# MagusConnectors.net
KiCad netlist of a schematic drawn in EAGLE
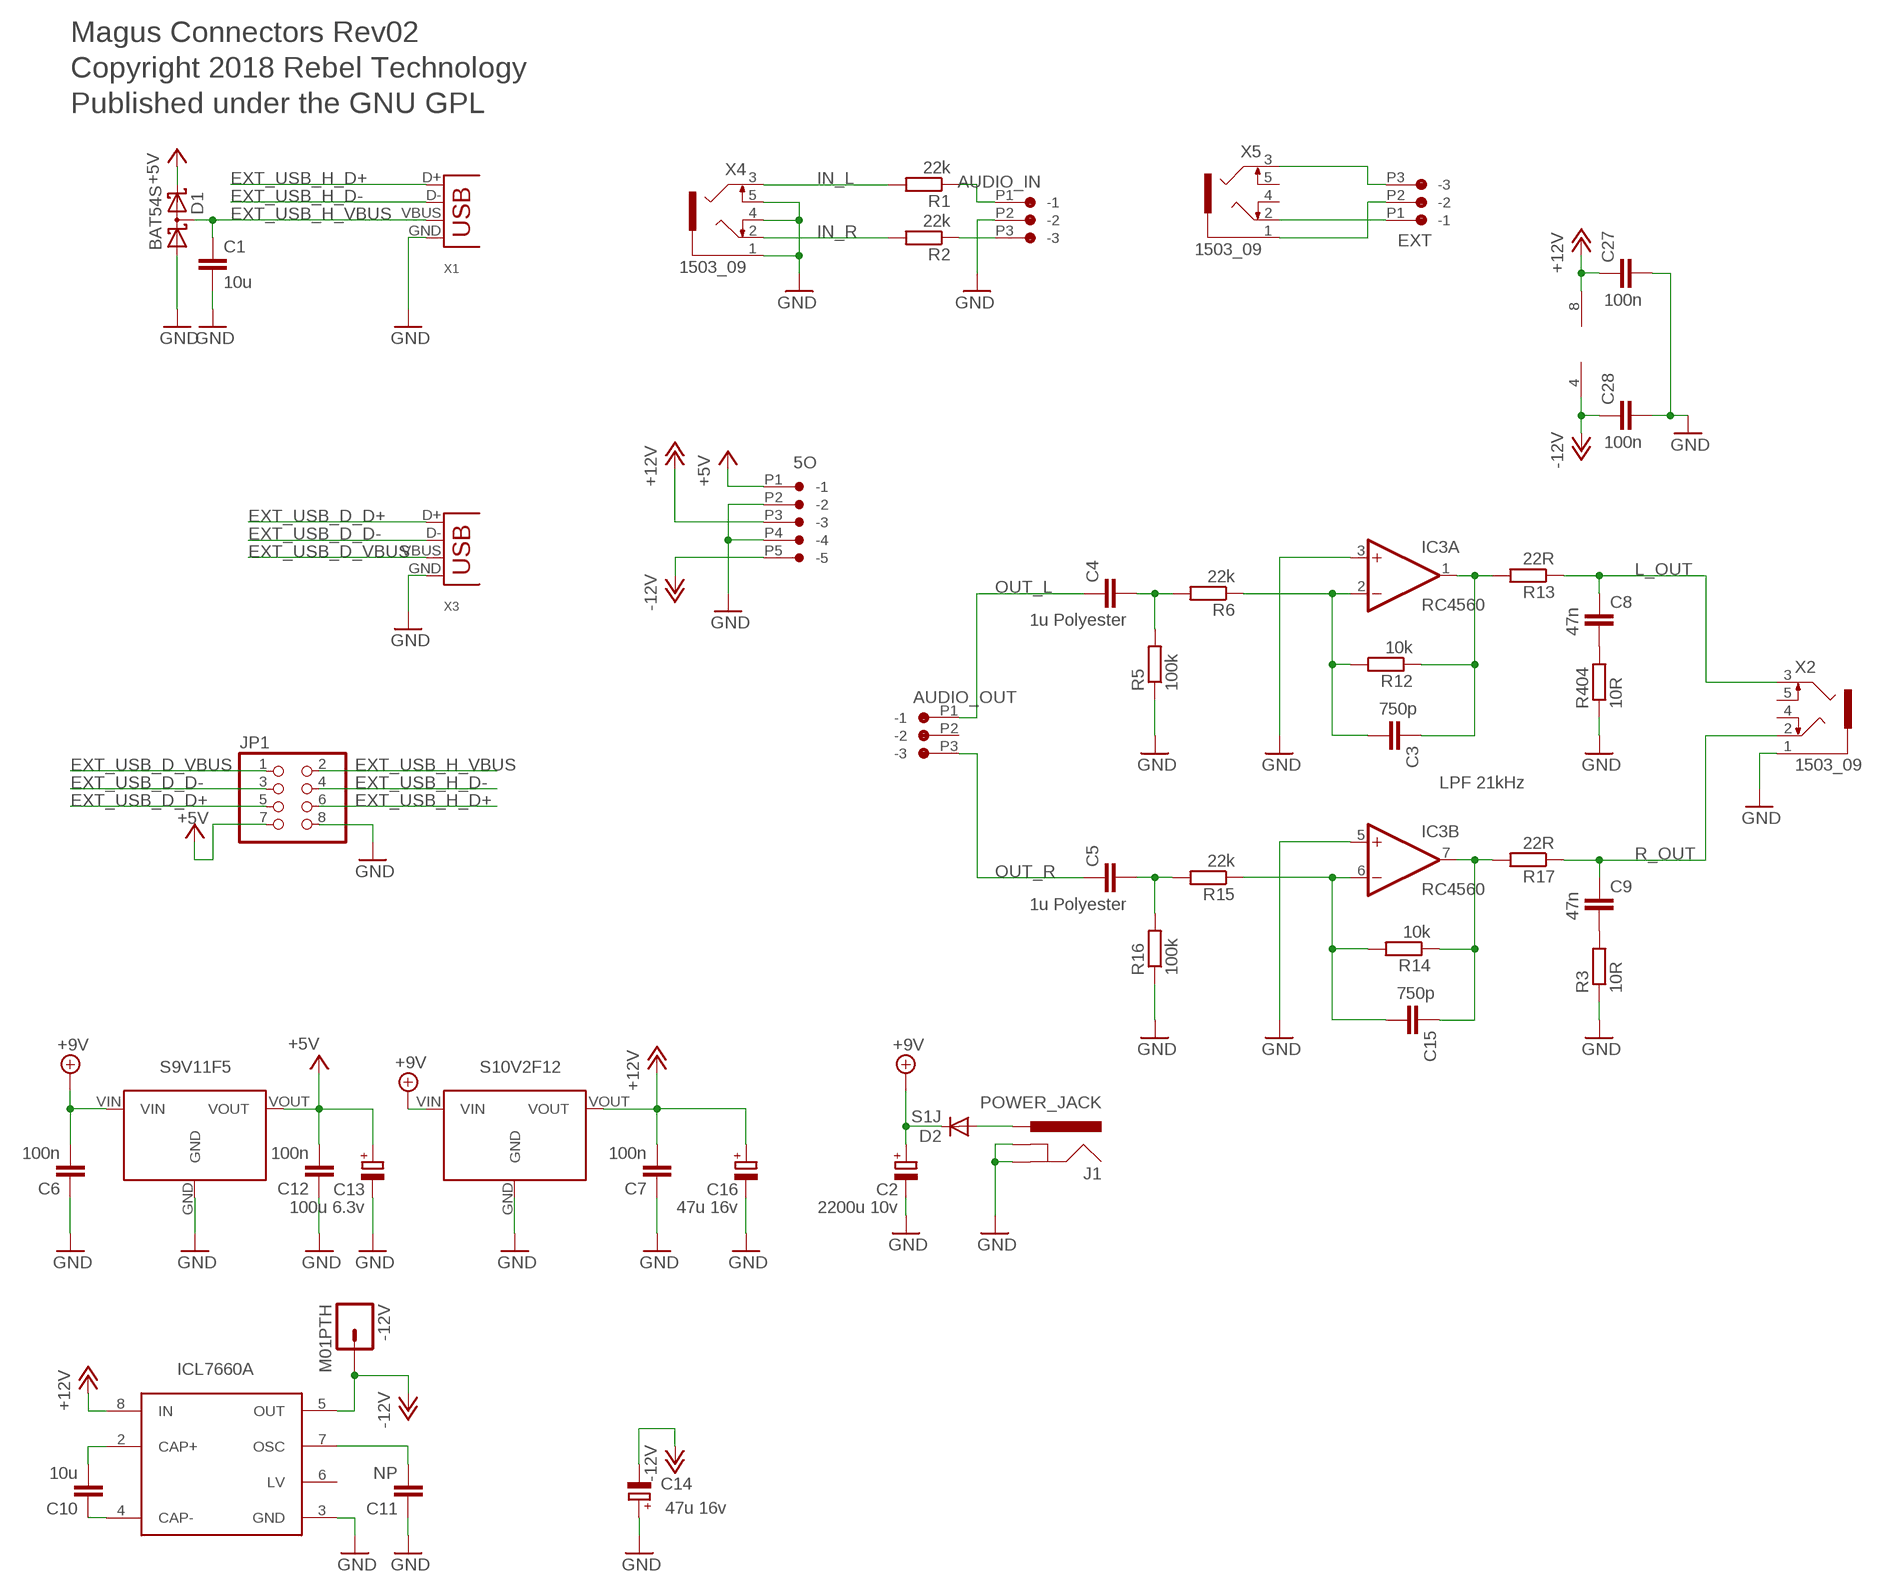
[diagram p0: schematic, sheet 1]

(export (version "E")
  (design (tool "Eeschema 10.0.6"))
  (components
    (comp (ref "-12V")
      (value "M01PTH")
      (footprint "eagle-import:1X01")
      (libsource (lib "eagle-import") (part "M01PTH"))
    )
    (comp (ref "5O")
      (value "CON-JST_PH_5W")
      (footprint "eagle-import:CON-JST_PH_5W")
      (libsource (lib "eagle-import") (part "CON-JST_PH_5W"))
    )
    (comp (ref "AUDIO_IN")
      (value "CON-JST_PH_3W")
      (footprint "eagle-import:CON-JST_PH_3W")
      (libsource (lib "eagle-import") (part "CON-JST_PH_3W"))
    )
    (comp (ref "AUDIO_OUT")
      (value "CON-JST_PH_3W")
      (footprint "eagle-import:CON-JST_PH_3W")
      (libsource (lib "eagle-import") (part "CON-JST_PH_3W"))
    )
    (comp (ref "C1")
      (value "10u")
      (footprint "eagle-import:C1206")
      (libsource (lib "eagle-import") (part "C-EUC1206"))
    )
    (comp (ref "C2")
      (value "2200u 10v")
      (footprint "eagle-import:PANASONIC_D")
      (libsource (lib "eagle-import") (part "CPOL-EUD"))
    )
    (comp (ref "C3")
      (value "750p")
      (footprint "eagle-import:C0603")
      (libsource (lib "eagle-import") (part "C-EUC0603"))
    )
    (comp (ref "C4")
      (value "1u Polyester")
      (footprint "eagle-import:C1210")
      (libsource (lib "eagle-import") (part "C-EUC1210"))
    )
    (comp (ref "C5")
      (value "1u Polyester")
      (footprint "eagle-import:C1210")
      (libsource (lib "eagle-import") (part "C-EUC1210"))
    )
    (comp (ref "C6")
      (value "100n")
      (footprint "eagle-import:C0603")
      (libsource (lib "eagle-import") (part "rcl_C-EUC0603"))
    )
    (comp (ref "C7")
      (value "100n")
      (footprint "eagle-import:C0603")
      (libsource (lib "eagle-import") (part "rcl_C-EUC0603"))
    )
    (comp (ref "C8")
      (value "47n")
      (footprint "eagle-import:C0603")
      (libsource (lib "eagle-import") (part "C-EUC0603"))
    )
    (comp (ref "C9")
      (value "47n")
      (footprint "eagle-import:C0603")
      (libsource (lib "eagle-import") (part "C-EUC0603"))
    )
    (comp (ref "C10")
      (value "10u")
      (footprint "eagle-import:C1206")
      (libsource (lib "eagle-import") (part "rcl_C-EUC1206"))
    )
    (comp (ref "C11")
      (value "NP")
      (footprint "eagle-import:C0603")
      (libsource (lib "eagle-import") (part "rcl_C-EUC0603"))
    )
    (comp (ref "C12")
      (value "100n")
      (footprint "eagle-import:C0603")
      (libsource (lib "eagle-import") (part "rcl_C-EUC0603"))
    )
    (comp (ref "C13")
      (value "100u 6.3v")
      (footprint "eagle-import:PANASONIC_B")
      (libsource (lib "eagle-import") (part "CPOL-EUB"))
    )
    (comp (ref "C14")
      (value "47u 16v")
      (footprint "eagle-import:PANASONIC_B")
      (libsource (lib "eagle-import") (part "CPOL-EUB"))
    )
    (comp (ref "C15")
      (value "750p")
      (footprint "eagle-import:C0603")
      (libsource (lib "eagle-import") (part "C-EUC0603"))
    )
    (comp (ref "C16")
      (value "47u 16v")
      (footprint "eagle-import:PANASONIC_B")
      (libsource (lib "eagle-import") (part "CPOL-EUB"))
    )
    (comp (ref "C27")
      (value "100n")
      (footprint "eagle-import:C0603")
      (libsource (lib "eagle-import") (part "C-EUC0603"))
    )
    (comp (ref "C28")
      (value "100n")
      (footprint "eagle-import:C0603")
      (libsource (lib "eagle-import") (part "C-EUC0603"))
    )
    (comp (ref "D1")
      (value "BAT54S")
      (footprint "eagle-import:SOT23")
      (libsource (lib "eagle-import") (part "BAT54S"))
    )
    (comp (ref "D2")
      (value "S1J")
      (footprint "eagle-import:SMA-DIODE")
      (libsource (lib "eagle-import") (part "DIODESMA"))
    )
    (comp (ref "EXT")
      (value "CON-JST_PH_3W")
      (footprint "eagle-import:CON-JST_PH_3W")
      (libsource (lib "eagle-import") (part "CON-JST_PH_3W"))
    )
    (comp (ref "IC3")
      (value "RC4560")
      (footprint "eagle-import:SO08")
      (libsource (lib "eagle-import") (part "NE5532D"))
    )
    (comp (ref "J1")
      (value "POWER_JACK")
      (footprint "eagle-import:DC_JACK_SLOT")
      (libsource (lib "eagle-import") (part "POWER_JACK"))
    )
    (comp (ref "JP1")
      (value "PINHD-2X4")
      (footprint "eagle-import:2X04")
      (libsource (lib "eagle-import") (part "PINHD-2X4"))
    )
    (comp (ref "R1")
      (value "22k")
      (footprint "eagle-import:R0603")
      (libsource (lib "eagle-import") (part "R-EU_R0603"))
    )
    (comp (ref "R2")
      (value "22k")
      (footprint "eagle-import:R0603")
      (libsource (lib "eagle-import") (part "R-EU_R0603"))
    )
    (comp (ref "R3")
      (value "10R")
      (footprint "eagle-import:R0603")
      (libsource (lib "eagle-import") (part "R-EU_R0603"))
    )
    (comp (ref "R5")
      (value "100k")
      (footprint "eagle-import:R0603")
      (libsource (lib "eagle-import") (part "R-EU_R0603"))
    )
    (comp (ref "R6")
      (value "22k")
      (footprint "eagle-import:R0603")
      (libsource (lib "eagle-import") (part "R-EU_R0603"))
    )
    (comp (ref "R12")
      (value "10k")
      (footprint "eagle-import:R0603")
      (libsource (lib "eagle-import") (part "R-EU_R0603"))
    )
    (comp (ref "R13")
      (value "22R")
      (footprint "eagle-import:R0603")
      (libsource (lib "eagle-import") (part "R-EU_R0603"))
    )
    (comp (ref "R14")
      (value "10k")
      (footprint "eagle-import:R0603")
      (libsource (lib "eagle-import") (part "R-EU_R0603"))
    )
    (comp (ref "R15")
      (value "22k")
      (footprint "eagle-import:R0603")
      (libsource (lib "eagle-import") (part "R-EU_R0603"))
    )
    (comp (ref "R16")
      (value "100k")
      (footprint "eagle-import:R0603")
      (libsource (lib "eagle-import") (part "R-EU_R0603"))
    )
    (comp (ref "R17")
      (value "22R")
      (footprint "eagle-import:R0603")
      (libsource (lib "eagle-import") (part "R-EU_R0603"))
    )
    (comp (ref "R404")
      (value "10R")
      (footprint "eagle-import:R0603")
      (libsource (lib "eagle-import") (part "R-EU_R0603"))
    )
    (comp (ref "U1")
      (value "S9V11F5")
      (footprint "eagle-import:REG_S9V11F5")
      (libsource (lib "eagle-import") (part "REG_S9V11F5"))
    )
    (comp (ref "U2")
      (value "S10V2F12")
      (footprint "eagle-import:REG_S9V11F5")
      (libsource (lib "eagle-import") (part "REG_S9V11F5"))
    )
    (comp (ref "U3")
      (value "ICL7660A")
      (footprint "eagle-import:SOIC8")
      (libsource (lib "eagle-import") (part "ICL7660"))
    )
    (comp (ref "X1")
      (value "USB-A-H")
      (footprint "eagle-import:USB-A-H")
      (libsource (lib "eagle-import") (part "USB-A-H"))
    )
    (comp (ref "X2")
      (value "1503_09")
      (footprint "eagle-import:1503_09")
      (libsource (lib "eagle-import") (part "1503_09"))
    )
    (comp (ref "X3")
      (value "USB-B-H")
      (footprint "eagle-import:USB-B-H")
      (libsource (lib "eagle-import") (part "USB-B-H"))
    )
    (comp (ref "X4")
      (value "1503_09")
      (footprint "eagle-import:1503_09")
      (libsource (lib "eagle-import") (part "1503_09"))
    )
    (comp (ref "X5")
      (value "1503_09")
      (footprint "eagle-import:1503_09")
      (libsource (lib "eagle-import") (part "1503_09"))
    )
  )
  (nets
    (net (code "1") (name "+5V") (class "Default")
      (node (ref "5O") (pin "P1") (pinfunction "-1_P1") (pintype "bidirectional"))
      (node (ref "C12") (pin "2") (pinfunction "2_2") (pintype "passive"))
      (node (ref "C13") (pin "+") (pinfunction "+_+") (pintype "passive"))
      (node (ref "D1") (pin "2") (pinfunction "C2_2") (pintype "passive"))
      (node (ref "JP1") (pin "7") (pinfunction "7_7") (pintype "passive"))
      (node (ref "U1") (pin "VOUT") (pinfunction "VOUT_VOUT") (pintype "output"))
    )
    (net (code "2") (name "+9V") (class "Default")
      (node (ref "C2") (pin "+") (pinfunction "+_+") (pintype "passive"))
      (node (ref "C6") (pin "2") (pinfunction "2_2") (pintype "passive"))
      (node (ref "D2") (pin "C") (pinfunction "C_C") (pintype "passive"))
      (node (ref "U1") (pin "VIN") (pinfunction "VIN_VIN") (pintype "input"))
      (node (ref "U2") (pin "VIN") (pinfunction "VIN_VIN") (pintype "input"))
    )
    (net (code "3") (name "+12V") (class "Default")
      (node (ref "5O") (pin "P3") (pinfunction "-3_P3") (pintype "bidirectional"))
      (node (ref "C16") (pin "+") (pinfunction "+_+") (pintype "passive"))
      (node (ref "C27") (pin "1") (pinfunction "1_1") (pintype "passive"))
      (node (ref "C7") (pin "2") (pinfunction "2_2") (pintype "passive"))
      (node (ref "IC3") (pin "8") (pinfunction "V+_8") (pintype "power_in"))
      (node (ref "U2") (pin "VOUT") (pinfunction "VOUT_VOUT") (pintype "output"))
      (node (ref "U3") (pin "8") (pinfunction "IN_8") (pintype "bidirectional"))
    )
    (net (code "4") (name "-12V") (class "Default")
      (node (ref "-12V") (pin "1") (pinfunction "1_1") (pintype "passive"))
      (node (ref "5O") (pin "P5") (pinfunction "-5_P5") (pintype "bidirectional"))
      (node (ref "C14") (pin "-") (pinfunction "-_-") (pintype "passive"))
      (node (ref "C28") (pin "1") (pinfunction "1_1") (pintype "passive"))
      (node (ref "IC3") (pin "4") (pinfunction "V-_4") (pintype "power_in"))
      (node (ref "U3") (pin "5") (pinfunction "OUT_5") (pintype "bidirectional"))
    )
    (net (code "5") (name "/EXT_USB_D_D+") (class "Default")
      (node (ref "JP1") (pin "5") (pinfunction "5_5") (pintype "passive"))
      (node (ref "X3") (pin "D+") (pinfunction "D+_D+") (pintype "bidirectional"))
    )
    (net (code "6") (name "/EXT_USB_D_D-") (class "Default")
      (node (ref "JP1") (pin "3") (pinfunction "3_3") (pintype "passive"))
      (node (ref "X3") (pin "D-") (pinfunction "D-_D-") (pintype "bidirectional"))
    )
    (net (code "7") (name "/EXT_USB_D_VBUS") (class "Default")
      (node (ref "JP1") (pin "1") (pinfunction "1_1") (pintype "passive"))
      (node (ref "X3") (pin "VBUS") (pinfunction "VBUS_VBUS") (pintype "bidirectional"))
    )
    (net (code "8") (name "/EXT_USB_H_D+") (class "Default")
      (node (ref "JP1") (pin "6") (pinfunction "6_6") (pintype "passive"))
      (node (ref "X1") (pin "D+") (pinfunction "D+_D+") (pintype "bidirectional"))
    )
    (net (code "9") (name "/EXT_USB_H_D-") (class "Default")
      (node (ref "JP1") (pin "4") (pinfunction "4_4") (pintype "passive"))
      (node (ref "X1") (pin "D-") (pinfunction "D-_D-") (pintype "bidirectional"))
    )
    (net (code "10") (name "/EXT_USB_H_VBUS") (class "Default")
      (node (ref "C1") (pin "1") (pinfunction "1_1") (pintype "passive"))
      (node (ref "D1") (pin "3") (pinfunction "C1A2_3") (pintype "passive"))
      (node (ref "JP1") (pin "2") (pinfunction "2_2") (pintype "passive"))
      (node (ref "X1") (pin "VBUS") (pinfunction "VBUS_VBUS") (pintype "bidirectional"))
    )
    (net (code "11") (name "/IN_L") (class "Default")
      (node (ref "R1") (pin "2") (pinfunction "2_2") (pintype "passive"))
      (node (ref "X4") (pin "3") (pinfunction "3_3") (pintype "passive"))
    )
    (net (code "12") (name "/IN_R") (class "Default")
      (node (ref "R2") (pin "2") (pinfunction "2_2") (pintype "passive"))
      (node (ref "X4") (pin "2") (pinfunction "2_2") (pintype "passive"))
    )
    (net (code "13") (name "/L_OUT") (class "Default")
      (node (ref "C8") (pin "1") (pinfunction "1_1") (pintype "passive"))
      (node (ref "R13") (pin "1") (pinfunction "1_1") (pintype "passive"))
      (node (ref "X2") (pin "3") (pinfunction "3_3") (pintype "passive"))
    )
    (net (code "14") (name "/OUT_L") (class "Default")
      (node (ref "AUDIO_OUT") (pin "P1") (pinfunction "-1_P1") (pintype "bidirectional"))
      (node (ref "C4") (pin "1") (pinfunction "1_1") (pintype "passive"))
    )
    (net (code "15") (name "/OUT_R") (class "Default")
      (node (ref "AUDIO_OUT") (pin "P3") (pinfunction "-3_P3") (pintype "bidirectional"))
      (node (ref "C5") (pin "1") (pinfunction "1_1") (pintype "passive"))
    )
    (net (code "16") (name "/R_OUT") (class "Default")
      (node (ref "C9") (pin "1") (pinfunction "1_1") (pintype "passive"))
      (node (ref "R17") (pin "1") (pinfunction "1_1") (pintype "passive"))
      (node (ref "X2") (pin "2") (pinfunction "2_2") (pintype "passive"))
    )
    (net (code "17") (name "GND") (class "Default")
      (node (ref "5O") (pin "P2") (pinfunction "-2_P2") (pintype "bidirectional"))
      (node (ref "5O") (pin "P4") (pinfunction "-4_P4") (pintype "bidirectional"))
      (node (ref "AUDIO_IN") (pin "P2") (pinfunction "-2_P2") (pintype "bidirectional"))
      (node (ref "C1") (pin "2") (pinfunction "2_2") (pintype "passive"))
      (node (ref "C11") (pin "1") (pinfunction "1_1") (pintype "passive"))
      (node (ref "C12") (pin "1") (pinfunction "1_1") (pintype "passive"))
      (node (ref "C13") (pin "-") (pinfunction "-_-") (pintype "passive"))
      (node (ref "C14") (pin "+") (pinfunction "+_+") (pintype "passive"))
      (node (ref "C16") (pin "-") (pinfunction "-_-") (pintype "passive"))
      (node (ref "C2") (pin "-") (pinfunction "-_-") (pintype "passive"))
      (node (ref "C27") (pin "2") (pinfunction "2_2") (pintype "passive"))
      (node (ref "C28") (pin "2") (pinfunction "2_2") (pintype "passive"))
      (node (ref "C6") (pin "1") (pinfunction "1_1") (pintype "passive"))
      (node (ref "C7") (pin "1") (pinfunction "1_1") (pintype "passive"))
      (node (ref "D1") (pin "1") (pinfunction "A1_1") (pintype "passive"))
      (node (ref "IC3") (pin "3") (pinfunction "+IN_3") (pintype "input"))
      (node (ref "IC3") (pin "5") (pinfunction "+IN_5") (pintype "input"))
      (node (ref "J1") (pin "GND") (pinfunction "GND_GND") (pintype "bidirectional"))
      (node (ref "J1") (pin "GNDBREAK") (pinfunction "GNDBREAK_GNDBREAK") (pintype "bidirectional"))
      (node (ref "JP1") (pin "8") (pinfunction "8_8") (pintype "passive"))
      (node (ref "R16") (pin "1") (pinfunction "1_1") (pintype "passive"))
      (node (ref "R3") (pin "1") (pinfunction "1_1") (pintype "passive"))
      (node (ref "R404") (pin "1") (pinfunction "1_1") (pintype "passive"))
      (node (ref "R5") (pin "1") (pinfunction "1_1") (pintype "passive"))
      (node (ref "U1") (pin "GND") (pinfunction "GND_GND") (pintype "power_in"))
      (node (ref "U2") (pin "GND") (pinfunction "GND_GND") (pintype "power_in"))
      (node (ref "U3") (pin "3") (pinfunction "GND_3") (pintype "bidirectional"))
      (node (ref "X1") (pin "GND") (pinfunction "GND_GND") (pintype "bidirectional"))
      (node (ref "X2") (pin "1") (pinfunction "1_1") (pintype "passive"))
      (node (ref "X3") (pin "GND") (pinfunction "GND_GND") (pintype "bidirectional"))
      (node (ref "X4") (pin "1") (pinfunction "1_1") (pintype "passive"))
      (node (ref "X4") (pin "4") (pinfunction "4_4") (pintype "passive"))
      (node (ref "X4") (pin "5") (pinfunction "5_5") (pintype "passive"))
    )
    (net (code "18") (name "Net-(AUDIO_IN--1)") (class "Default")
      (node (ref "AUDIO_IN") (pin "P1") (pinfunction "-1_P1") (pintype "bidirectional"))
      (node (ref "R1") (pin "1") (pinfunction "1_1") (pintype "passive"))
    )
    (net (code "19") (name "Net-(AUDIO_IN--3)") (class "Default")
      (node (ref "AUDIO_IN") (pin "P3") (pinfunction "-3_P3") (pintype "bidirectional"))
      (node (ref "R2") (pin "1") (pinfunction "1_1") (pintype "passive"))
    )
    (net (code "20") (name "Net-(C4-Pad2)") (class "Default")
      (node (ref "C4") (pin "2") (pinfunction "2_2") (pintype "passive"))
      (node (ref "R5") (pin "2") (pinfunction "2_2") (pintype "passive"))
      (node (ref "R6") (pin "2") (pinfunction "2_2") (pintype "passive"))
    )
    (net (code "21") (name "Net-(C5-Pad2)") (class "Default")
      (node (ref "C5") (pin "2") (pinfunction "2_2") (pintype "passive"))
      (node (ref "R15") (pin "2") (pinfunction "2_2") (pintype "passive"))
      (node (ref "R16") (pin "2") (pinfunction "2_2") (pintype "passive"))
    )
    (net (code "22") (name "Net-(C8-Pad2)") (class "Default")
      (node (ref "C8") (pin "2") (pinfunction "2_2") (pintype "passive"))
      (node (ref "R404") (pin "2") (pinfunction "2_2") (pintype "passive"))
    )
    (net (code "23") (name "Net-(C9-Pad2)") (class "Default")
      (node (ref "C9") (pin "2") (pinfunction "2_2") (pintype "passive"))
      (node (ref "R3") (pin "2") (pinfunction "2_2") (pintype "passive"))
    )
    (net (code "24") (name "Net-(D2-PadA)") (class "Default")
      (node (ref "D2") (pin "A") (pinfunction "A_A") (pintype "passive"))
      (node (ref "J1") (pin "PWR") (pinfunction "PWR_PWR") (pintype "bidirectional"))
    )
    (net (code "25") (name "Net-(EXT--1)") (class "Default")
      (node (ref "EXT") (pin "P1") (pinfunction "-1_P1") (pintype "bidirectional"))
      (node (ref "X5") (pin "2") (pinfunction "2_2") (pintype "passive"))
    )
    (net (code "26") (name "Net-(EXT--2)") (class "Default")
      (node (ref "EXT") (pin "P2") (pinfunction "-2_P2") (pintype "bidirectional"))
      (node (ref "X5") (pin "1") (pinfunction "1_1") (pintype "passive"))
    )
    (net (code "27") (name "Net-(EXT--3)") (class "Default")
      (node (ref "EXT") (pin "P3") (pinfunction "-3_P3") (pintype "bidirectional"))
      (node (ref "X5") (pin "3") (pinfunction "3_3") (pintype "passive"))
    )
    (net (code "28") (name "Net-(IC3A--IN)") (class "Default")
      (node (ref "C3") (pin "2") (pinfunction "2_2") (pintype "passive"))
      (node (ref "IC3") (pin "2") (pinfunction "-IN_2") (pintype "input"))
      (node (ref "R12") (pin "2") (pinfunction "2_2") (pintype "passive"))
      (node (ref "R6") (pin "1") (pinfunction "1_1") (pintype "passive"))
    )
    (net (code "29") (name "Net-(IC3A-OUT)") (class "Default")
      (node (ref "C3") (pin "1") (pinfunction "1_1") (pintype "passive"))
      (node (ref "IC3") (pin "1") (pinfunction "OUT_1") (pintype "output"))
      (node (ref "R12") (pin "1") (pinfunction "1_1") (pintype "passive"))
      (node (ref "R13") (pin "2") (pinfunction "2_2") (pintype "passive"))
    )
    (net (code "30") (name "Net-(IC3B--IN)") (class "Default")
      (node (ref "C15") (pin "2") (pinfunction "2_2") (pintype "passive"))
      (node (ref "IC3") (pin "6") (pinfunction "-IN_6") (pintype "input"))
      (node (ref "R14") (pin "2") (pinfunction "2_2") (pintype "passive"))
      (node (ref "R15") (pin "1") (pinfunction "1_1") (pintype "passive"))
    )
    (net (code "31") (name "Net-(IC3B-OUT)") (class "Default")
      (node (ref "C15") (pin "1") (pinfunction "1_1") (pintype "passive"))
      (node (ref "IC3") (pin "7") (pinfunction "OUT_7") (pintype "output"))
      (node (ref "R14") (pin "1") (pinfunction "1_1") (pintype "passive"))
      (node (ref "R17") (pin "2") (pinfunction "2_2") (pintype "passive"))
    )
    (net (code "32") (name "Net-(U3-CAP+)") (class "Default")
      (node (ref "C10") (pin "2") (pinfunction "2_2") (pintype "passive"))
      (node (ref "U3") (pin "2") (pinfunction "CAP+_2") (pintype "bidirectional"))
    )
    (net (code "33") (name "Net-(U3-CAP-)") (class "Default")
      (node (ref "C10") (pin "1") (pinfunction "1_1") (pintype "passive"))
      (node (ref "U3") (pin "4") (pinfunction "CAP-_4") (pintype "bidirectional"))
    )
    (net (code "34") (name "Net-(U3-OSC)") (class "Default")
      (node (ref "C11") (pin "2") (pinfunction "2_2") (pintype "passive"))
      (node (ref "U3") (pin "7") (pinfunction "OSC_7") (pintype "bidirectional"))
    )
    (net (code "35") (name "unconnected-(AUDIO_OUT--2-PadP2)") (class "Default")
      (node (ref "AUDIO_OUT") (pin "P2") (pinfunction "-2_P2") (pintype "bidirectional"))
    )
    (net (code "36") (name "unconnected-(U3-LV-Pad6)") (class "Default")
      (node (ref "U3") (pin "6") (pinfunction "LV_6") (pintype "bidirectional"))
    )
    (net (code "37") (name "unconnected-(X2-Pad4)") (class "Default")
      (node (ref "X2") (pin "4") (pinfunction "4_4") (pintype "passive"))
    )
    (net (code "38") (name "unconnected-(X2-Pad5)") (class "Default")
      (node (ref "X2") (pin "5") (pinfunction "5_5") (pintype "passive"))
    )
    (net (code "39") (name "unconnected-(X5-Pad4)") (class "Default")
      (node (ref "X5") (pin "4") (pinfunction "4_4") (pintype "passive"))
    )
    (net (code "40") (name "unconnected-(X5-Pad5)") (class "Default")
      (node (ref "X5") (pin "5") (pinfunction "5_5") (pintype "passive"))
    )
  )
)
